# motor.net
KiCad netlist of a schematic drawn in EAGLE
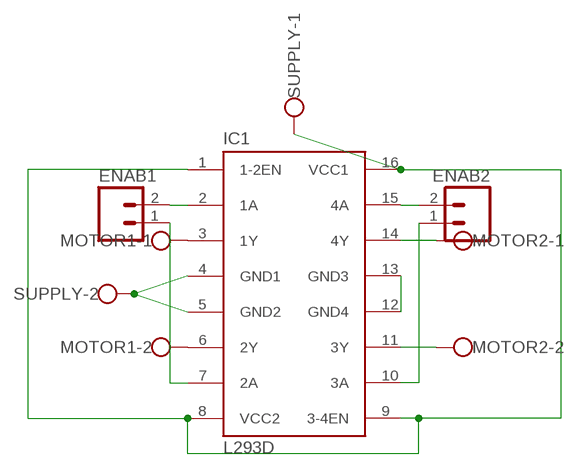
[diagram p0: schematic, sheet 1]

(export (version "E")
  (design (tool "Eeschema 10.0.6"))
  (components
    (comp (ref "ENAB1")
      (value "M02PTH3")
      (footprint "eagle-import:1X02_LONGPADS")
      (libsource (lib "eagle-import") (part "M02PTH3"))
    )
    (comp (ref "ENAB2")
      (value "M02PTH3")
      (footprint "eagle-import:1X02_LONGPADS")
      (libsource (lib "eagle-import") (part "M02PTH3"))
    )
    (comp (ref "IC1")
      (value "L293D")
      (footprint "eagle-import:DIL16")
      (libsource (lib "eagle-import") (part "L293D"))
    )
    (comp (ref "MOTOR1")
      (value "W237-102")
      (footprint "eagle-import:W237-102")
      (fields (field (name "MPN") "237-102"))
      (libsource (lib "eagle-import") (part "W237-102"))
    )
    (comp (ref "MOTOR2")
      (value "W237-102")
      (footprint "eagle-import:W237-102")
      (fields (field (name "MPN") "237-102"))
      (libsource (lib "eagle-import") (part "W237-102"))
    )
    (comp (ref "SUPPLY")
      (value "W237-102")
      (footprint "eagle-import:W237-102")
      (fields (field (name "MPN") "237-102"))
      (libsource (lib "eagle-import") (part "W237-102"))
    )
  )
  (nets
    (net (code "1") (name "Net-(IC1-1-2EN)") (class "Default")
      (node (ref "IC1") (pin "1") (pinfunction "1-2EN_1") (pintype "input"))
      (node (ref "IC1") (pin "16") (pinfunction "VCC1_16") (pintype "power_in"))
      (node (ref "IC1") (pin "8") (pinfunction "VCC2_8") (pintype "power_in"))
      (node (ref "IC1") (pin "9") (pinfunction "3-4EN_9") (pintype "input"))
      (node (ref "SUPPLY") (pin "1") (pinfunction "KL_1") (pintype "passive"))
    )
    (net (code "2") (name "Net-(IC1-1A)") (class "Default")
      (node (ref "ENAB1") (pin "2") (pinfunction "2_2") (pintype "passive"))
      (node (ref "IC1") (pin "2") (pinfunction "1A_2") (pintype "input"))
    )
    (net (code "3") (name "Net-(IC1-1Y)") (class "Default")
      (node (ref "IC1") (pin "3") (pinfunction "1Y_3") (pintype "output"))
      (node (ref "MOTOR1") (pin "1") (pinfunction "KL_1") (pintype "passive"))
    )
    (net (code "4") (name "Net-(IC1-2A)") (class "Default")
      (node (ref "ENAB1") (pin "1") (pinfunction "1_1") (pintype "passive"))
      (node (ref "IC1") (pin "7") (pinfunction "2A_7") (pintype "input"))
    )
    (net (code "5") (name "Net-(IC1-2Y)") (class "Default")
      (node (ref "IC1") (pin "6") (pinfunction "2Y_6") (pintype "output"))
      (node (ref "MOTOR1") (pin "2") (pinfunction "KL_2") (pintype "passive"))
    )
    (net (code "6") (name "Net-(IC1-3A)") (class "Default")
      (node (ref "ENAB2") (pin "1") (pinfunction "1_1") (pintype "passive"))
      (node (ref "IC1") (pin "10") (pinfunction "3A_10") (pintype "input"))
    )
    (net (code "7") (name "Net-(IC1-3Y)") (class "Default")
      (node (ref "IC1") (pin "11") (pinfunction "3Y_11") (pintype "output"))
      (node (ref "MOTOR2") (pin "2") (pinfunction "KL_2") (pintype "passive"))
    )
    (net (code "8") (name "Net-(IC1-4A)") (class "Default")
      (node (ref "ENAB2") (pin "2") (pinfunction "2_2") (pintype "passive"))
      (node (ref "IC1") (pin "15") (pinfunction "4A_15") (pintype "input"))
    )
    (net (code "9") (name "Net-(IC1-4Y)") (class "Default")
      (node (ref "IC1") (pin "14") (pinfunction "4Y_14") (pintype "output"))
      (node (ref "MOTOR2") (pin "1") (pinfunction "KL_1") (pintype "passive"))
    )
    (net (code "10") (name "Net-(IC1-GND1)") (class "Default")
      (node (ref "IC1") (pin "4") (pinfunction "GND1_4") (pintype "power_in"))
      (node (ref "IC1") (pin "5") (pinfunction "GND2_5") (pintype "power_in"))
      (node (ref "SUPPLY") (pin "2") (pinfunction "KL_2") (pintype "passive"))
    )
    (net (code "11") (name "Net-(IC1-GND3)") (class "Default")
      (node (ref "IC1") (pin "12") (pinfunction "GND4_12") (pintype "power_in"))
      (node (ref "IC1") (pin "13") (pinfunction "GND3_13") (pintype "power_in"))
    )
  )
)
